# design.net
KiCad netlist of a schematic drawn in Altium Designer
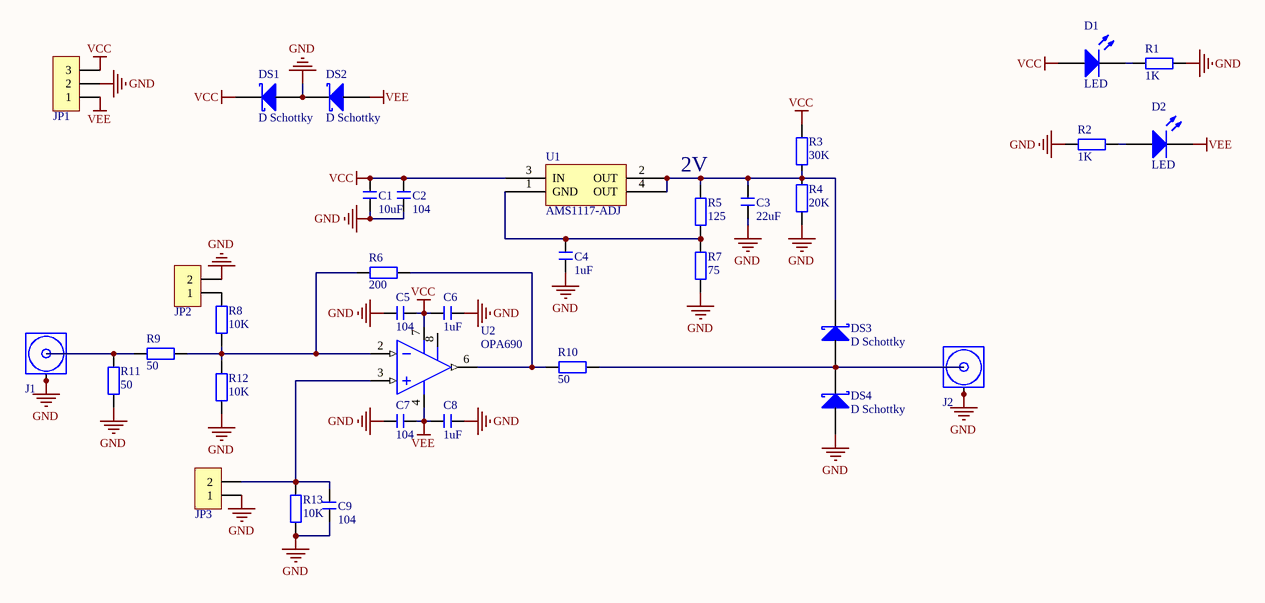
[diagram p0: 调偏电路.SchDoc]

(export (version "E")
  (design (tool "Eeschema 10.0.6"))
  (components
    (comp (ref "C1")
      (value "10uF")
      (footprint "C 0805")
      (description "无极性贴片电容")
      (fields (field (name "版权归属") "源创客"))
      (libsource (lib "电阻-电容-电感") (part "C"))
    )
    (comp (ref "C2")
      (value "104")
      (footprint "C 0603")
      (description "无极性贴片电容")
      (fields (field (name "版权归属") "源创客"))
      (libsource (lib "电阻-电容-电感") (part "C"))
    )
    (comp (ref "C3")
      (value "22uF")
      (footprint "C 0805")
      (description "无极性贴片电容")
      (fields (field (name "版权归属") "源创客"))
      (libsource (lib "电阻-电容-电感") (part "C"))
    )
    (comp (ref "C4")
      (value "1uF")
      (footprint "C 0805")
      (description "无极性贴片电容")
      (fields (field (name "版权归属") "源创客"))
      (libsource (lib "电阻-电容-电感") (part "C"))
    )
    (comp (ref "C5")
      (value "104")
      (footprint "C 0603")
      (description "无极性贴片电容")
      (fields (field (name "版权归属") "源创客"))
      (libsource (lib "电阻-电容-电感") (part "C"))
    )
    (comp (ref "C6")
      (value "1uF")
      (footprint "C 0603")
      (description "无极性贴片电容")
      (fields (field (name "版权归属") "源创客"))
      (libsource (lib "电阻-电容-电感") (part "C"))
    )
    (comp (ref "C7")
      (value "104")
      (footprint "C 0603")
      (description "无极性贴片电容")
      (fields (field (name "版权归属") "源创客"))
      (libsource (lib "电阻-电容-电感") (part "C"))
    )
    (comp (ref "C8")
      (value "1uF")
      (footprint "C 0603")
      (description "无极性贴片电容")
      (fields (field (name "版权归属") "源创客"))
      (libsource (lib "电阻-电容-电感") (part "C"))
    )
    (comp (ref "C9")
      (value "104")
      (footprint "C 0603")
      (description "无极性贴片电容")
      (fields (field (name "版权归属") "源创客"))
      (libsource (lib "电阻-电容-电感") (part "C"))
    )
    (comp (ref "D1")
      (value "LED")
      (footprint "LED_0805")
      (description "发光二极管")
      (fields (field (name "PUBLISHER") "Altium Limited"))
      (libsource (lib "LIB") (part "LED"))
    )
    (comp (ref "D2")
      (value "LED")
      (footprint "LED_0805")
      (description "发光二极管")
      (fields (field (name "PUBLISHER") "Altium Limited"))
      (libsource (lib "LIB") (part "LED"))
    )
    (comp (ref "DS1")
      (value "D Schottky")
      (footprint "DIODE-SMA")
      (description "Schottky Diode")
      (fields (field (name "PUBLISHER") "Altium Limited"))
      (libsource (lib "LIB") (part "D Schottky"))
    )
    (comp (ref "DS2")
      (value "D Schottky")
      (footprint "DIODE-SMA")
      (description "Schottky Diode")
      (fields (field (name "PUBLISHER") "Altium Limited"))
      (libsource (lib "LIB") (part "D Schottky"))
    )
    (comp (ref "DS3")
      (value "D Schottky")
      (footprint "DIODE-SMA")
      (description "Schottky Diode")
      (fields (field (name "PUBLISHER") "Altium Limited"))
      (libsource (lib "LIB") (part "D Schottky"))
    )
    (comp (ref "DS4")
      (value "D Schottky")
      (footprint "DIODE-SMA")
      (description "Schottky Diode")
      (fields (field (name "PUBLISHER") "Altium Limited"))
      (libsource (lib "LIB") (part "D Schottky"))
    )
    (comp (ref "J1") (value "COAX") (footprint "MCX5.08-5-H") (libsource (lib "LIB") (part "COAX")))
    (comp (ref "J2") (value "COAX") (footprint "MCX5.08-5-H") (libsource (lib "LIB") (part "COAX")))
    (comp (ref "JP1")
      (value "HDR-1X3")
      (footprint "XH2.54-3P_H")
      (description "3P接插件")
      (fields (field (name "版权归属") "源创客"))
      (libsource (lib "接插件") (part "Header 3"))
    )
    (comp (ref "JP2")
      (value "HDR-1X2")
      (footprint "HDR-1X2")
      (description "2P接插件")
      (fields (field (name "版权归属") "源创客"))
      (libsource (lib "接插件") (part "Header 2"))
    )
    (comp (ref "JP3")
      (value "HDR-1X2")
      (footprint "HDR-1X2")
      (description "2P接插件")
      (fields (field (name "版权归属") "源创客"))
      (libsource (lib "接插件") (part "Header 2"))
    )
    (comp (ref "R1")
      (value "1K")
      (footprint "R 0805")
      (description "贴片电阻")
      (fields (field (name "版权归属") "源创客"))
      (libsource (lib "电阻-电容-电感") (part "R"))
    )
    (comp (ref "R2")
      (value "1K")
      (footprint "R 0805")
      (description "贴片电阻")
      (fields (field (name "版权归属") "源创客"))
      (libsource (lib "电阻-电容-电感") (part "R"))
    )
    (comp (ref "R3")
      (value "30K")
      (footprint "R 0603")
      (description "贴片电阻")
      (fields (field (name "版权归属") "源创客"))
      (libsource (lib "电阻-电容-电感") (part "R"))
    )
    (comp (ref "R4")
      (value "20K")
      (footprint "R 0603")
      (description "贴片电阻")
      (fields (field (name "版权归属") "源创客"))
      (libsource (lib "电阻-电容-电感") (part "R"))
    )
    (comp (ref "R5")
      (value "125")
      (footprint "R 0603")
      (description "贴片电阻")
      (fields (field (name "版权归属") "源创客"))
      (libsource (lib "电阻-电容-电感") (part "R"))
    )
    (comp (ref "R6")
      (value "200")
      (footprint "R 0603")
      (description "贴片电阻")
      (fields (field (name "版权归属") "源创客"))
      (libsource (lib "电阻-电容-电感") (part "R"))
    )
    (comp (ref "R7")
      (value "75")
      (footprint "R 0603")
      (description "贴片电阻")
      (fields (field (name "版权归属") "源创客"))
      (libsource (lib "电阻-电容-电感") (part "R"))
    )
    (comp (ref "R8")
      (value "10K")
      (footprint "R 0603")
      (description "贴片电阻")
      (fields (field (name "版权归属") "源创客"))
      (libsource (lib "电阻-电容-电感") (part "R"))
    )
    (comp (ref "R9")
      (value "50")
      (footprint "R 0603")
      (description "贴片电阻")
      (fields (field (name "版权归属") "源创客"))
      (libsource (lib "电阻-电容-电感") (part "R"))
    )
    (comp (ref "R10")
      (value "50")
      (footprint "R 0603")
      (description "贴片电阻")
      (fields (field (name "版权归属") "源创客"))
      (libsource (lib "电阻-电容-电感") (part "R"))
    )
    (comp (ref "R11")
      (value "50")
      (footprint "R 0603")
      (description "贴片电阻")
      (fields (field (name "版权归属") "源创客"))
      (libsource (lib "电阻-电容-电感") (part "R"))
    )
    (comp (ref "R12")
      (value "10K")
      (footprint "R 0603")
      (description "贴片电阻")
      (fields (field (name "版权归属") "源创客"))
      (libsource (lib "电阻-电容-电感") (part "R"))
    )
    (comp (ref "R13")
      (value "10K")
      (footprint "R 0603")
      (description "贴片电阻")
      (fields (field (name "版权归属") "源创客"))
      (libsource (lib "电阻-电容-电感") (part "R"))
    )
    (comp (ref "U1")
      (value "AMS1117-ADJ")
      (footprint "SOT223_N")
      (description "线性稳压芯片")
      (libsource (lib "LIB") (part "ASM1117"))
    )
    (comp (ref "U2")
      (value "OPA690")
      (footprint "LIB:SOIC8_N")
      (description "具有禁用功能的宽带电压反馈运算放大器")
      (libsource (lib "LIB") (part "OPA690ID"))
    )
  )
  (nets
    (net (code "1") (name "GND") (class "Default")
      (node (ref "C1") (pin "1") (pinfunction "1_1") (pintype "passive"))
      (node (ref "C2") (pin "1") (pinfunction "1_1") (pintype "passive"))
      (node (ref "C3") (pin "1") (pinfunction "1_1") (pintype "passive"))
      (node (ref "C4") (pin "1") (pinfunction "1_1") (pintype "passive"))
      (node (ref "C5") (pin "1") (pinfunction "1_1") (pintype "passive"))
      (node (ref "C6") (pin "2") (pinfunction "2_2") (pintype "passive"))
      (node (ref "C7") (pin "1") (pinfunction "1_1") (pintype "passive"))
      (node (ref "C8") (pin "2") (pinfunction "2_2") (pintype "passive"))
      (node (ref "C9") (pin "1") (pinfunction "1_1") (pintype "passive"))
      (node (ref "DS1") (pin "1") (pinfunction "1_1") (pintype "passive"))
      (node (ref "DS2") (pin "2") (pinfunction "2_2") (pintype "passive"))
      (node (ref "DS4") (pin "1") (pinfunction "1_1") (pintype "passive"))
      (node (ref "J1") (pin "2") (pinfunction "GND_2") (pintype "passive"))
      (node (ref "J1") (pin "3") (pinfunction "GND_3") (pintype "passive"))
      (node (ref "J1") (pin "4") (pinfunction "GND_4") (pintype "passive"))
      (node (ref "J1") (pin "5") (pinfunction "GND_5") (pintype "passive"))
      (node (ref "J2") (pin "2") (pinfunction "GND_2") (pintype "passive"))
      (node (ref "J2") (pin "3") (pinfunction "GND_3") (pintype "passive"))
      (node (ref "J2") (pin "4") (pinfunction "GND_4") (pintype "passive"))
      (node (ref "J2") (pin "5") (pinfunction "GND_5") (pintype "passive"))
      (node (ref "JP1") (pin "2") (pinfunction "2_2") (pintype "passive"))
      (node (ref "JP2") (pin "2") (pinfunction "2_2") (pintype "passive"))
      (node (ref "JP3") (pin "1") (pinfunction "1_1") (pintype "passive"))
      (node (ref "R1") (pin "2") (pinfunction "2_2") (pintype "passive"))
      (node (ref "R11") (pin "1") (pinfunction "1_1") (pintype "passive"))
      (node (ref "R12") (pin "1") (pinfunction "1_1") (pintype "passive"))
      (node (ref "R13") (pin "1") (pinfunction "1_1") (pintype "passive"))
      (node (ref "R2") (pin "1") (pinfunction "1_1") (pintype "passive"))
      (node (ref "R4") (pin "1") (pinfunction "1_1") (pintype "passive"))
      (node (ref "R7") (pin "1") (pinfunction "1_1") (pintype "passive"))
    )
    (net (code "2") (name "Net-(C3-Pad2)") (class "Default")
      (node (ref "C3") (pin "2") (pinfunction "2_2") (pintype "passive"))
      (node (ref "DS3") (pin "2") (pinfunction "2_2") (pintype "passive"))
      (node (ref "R3") (pin "2") (pinfunction "2_2") (pintype "passive"))
      (node (ref "R4") (pin "2") (pinfunction "2_2") (pintype "passive"))
      (node (ref "R5") (pin "1") (pinfunction "1_1") (pintype "passive"))
      (node (ref "U1") (pin "2") (pinfunction "OUT_2") (pintype "passive"))
      (node (ref "U1") (pin "4") (pinfunction "OUT_4") (pintype "passive"))
    )
    (net (code "3") (name "Net-(D1-K)") (class "Default")
      (node (ref "D1") (pin "2") (pinfunction "K_2") (pintype "passive"))
      (node (ref "R1") (pin "1") (pinfunction "1_1") (pintype "passive"))
    )
    (net (code "4") (name "Net-(D2-A)") (class "Default")
      (node (ref "D2") (pin "1") (pinfunction "A_1") (pintype "passive"))
      (node (ref "R2") (pin "2") (pinfunction "2_2") (pintype "passive"))
    )
    (net (code "5") (name "Net-(J1-Signal)") (class "Default")
      (node (ref "J1") (pin "1") (pinfunction "Signal_1") (pintype "passive"))
      (node (ref "R11") (pin "2") (pinfunction "2_2") (pintype "passive"))
      (node (ref "R9") (pin "1") (pinfunction "1_1") (pintype "passive"))
    )
    (net (code "6") (name "Net-(J2-Signal)") (class "Default")
      (node (ref "DS3") (pin "1") (pinfunction "1_1") (pintype "passive"))
      (node (ref "DS4") (pin "2") (pinfunction "2_2") (pintype "passive"))
      (node (ref "J2") (pin "1") (pinfunction "Signal_1") (pintype "passive"))
      (node (ref "R10") (pin "2") (pinfunction "2_2") (pintype "passive"))
    )
    (net (code "7") (name "Net-(JP2-Pad1)") (class "Default")
      (node (ref "JP2") (pin "1") (pinfunction "1_1") (pintype "passive"))
      (node (ref "R8") (pin "1") (pinfunction "1_1") (pintype "passive"))
    )
    (net (code "8") (name "Net-(U1-GND)") (class "Default")
      (node (ref "C4") (pin "2") (pinfunction "2_2") (pintype "passive"))
      (node (ref "R5") (pin "2") (pinfunction "2_2") (pintype "passive"))
      (node (ref "R7") (pin "2") (pinfunction "2_2") (pintype "passive"))
      (node (ref "U1") (pin "1") (pinfunction "GND_1") (pintype "passive"))
    )
    (net (code "9") (name "Net-(U2-IN+)") (class "Default")
      (node (ref "C9") (pin "2") (pinfunction "2_2") (pintype "passive"))
      (node (ref "JP3") (pin "2") (pinfunction "2_2") (pintype "passive"))
      (node (ref "R13") (pin "2") (pinfunction "2_2") (pintype "passive"))
      (node (ref "U2") (pin "3") (pinfunction "IN+_3") (pintype "input"))
    )
    (net (code "10") (name "Net-(U2-IN-)") (class "Default")
      (node (ref "R12") (pin "2") (pinfunction "2_2") (pintype "passive"))
      (node (ref "R6") (pin "1") (pinfunction "1_1") (pintype "passive"))
      (node (ref "R8") (pin "2") (pinfunction "2_2") (pintype "passive"))
      (node (ref "R9") (pin "2") (pinfunction "2_2") (pintype "passive"))
      (node (ref "U2") (pin "2") (pinfunction "IN-_2") (pintype "input"))
    )
    (net (code "11") (name "Net-(U2-OUT)") (class "Default")
      (node (ref "R10") (pin "1") (pinfunction "1_1") (pintype "passive"))
      (node (ref "R6") (pin "2") (pinfunction "2_2") (pintype "passive"))
      (node (ref "U2") (pin "6") (pinfunction "OUT_6") (pintype "output"))
    )
    (net (code "12") (name "VCC") (class "Default")
      (node (ref "C1") (pin "2") (pinfunction "2_2") (pintype "passive"))
      (node (ref "C2") (pin "2") (pinfunction "2_2") (pintype "passive"))
      (node (ref "C5") (pin "2") (pinfunction "2_2") (pintype "passive"))
      (node (ref "C6") (pin "1") (pinfunction "1_1") (pintype "passive"))
      (node (ref "D1") (pin "1") (pinfunction "A_1") (pintype "passive"))
      (node (ref "DS1") (pin "2") (pinfunction "2_2") (pintype "passive"))
      (node (ref "JP1") (pin "3") (pinfunction "3_3") (pintype "passive"))
      (node (ref "R3") (pin "1") (pinfunction "1_1") (pintype "passive"))
      (node (ref "U1") (pin "3") (pinfunction "IN_3") (pintype "passive"))
      (node (ref "U2") (pin "7") (pinfunction "V+_7") (pintype "power_in"))
    )
    (net (code "13") (name "VEE") (class "Default")
      (node (ref "C7") (pin "2") (pinfunction "2_2") (pintype "passive"))
      (node (ref "C8") (pin "1") (pinfunction "1_1") (pintype "passive"))
      (node (ref "D2") (pin "2") (pinfunction "K_2") (pintype "passive"))
      (node (ref "DS2") (pin "1") (pinfunction "1_1") (pintype "passive"))
      (node (ref "JP1") (pin "1") (pinfunction "1_1") (pintype "passive"))
      (node (ref "U2") (pin "4") (pinfunction "V-_4") (pintype "power_in"))
    )
    (net (code "14") (name "unconnected-(U2-DIS-Pad8)") (class "Default")
      (node (ref "U2") (pin "8") (pinfunction "DIS_8") (pintype "passive"))
    )
  )
)
